# ideas.net
KiCad netlist of a schematic drawn in Altium Designer
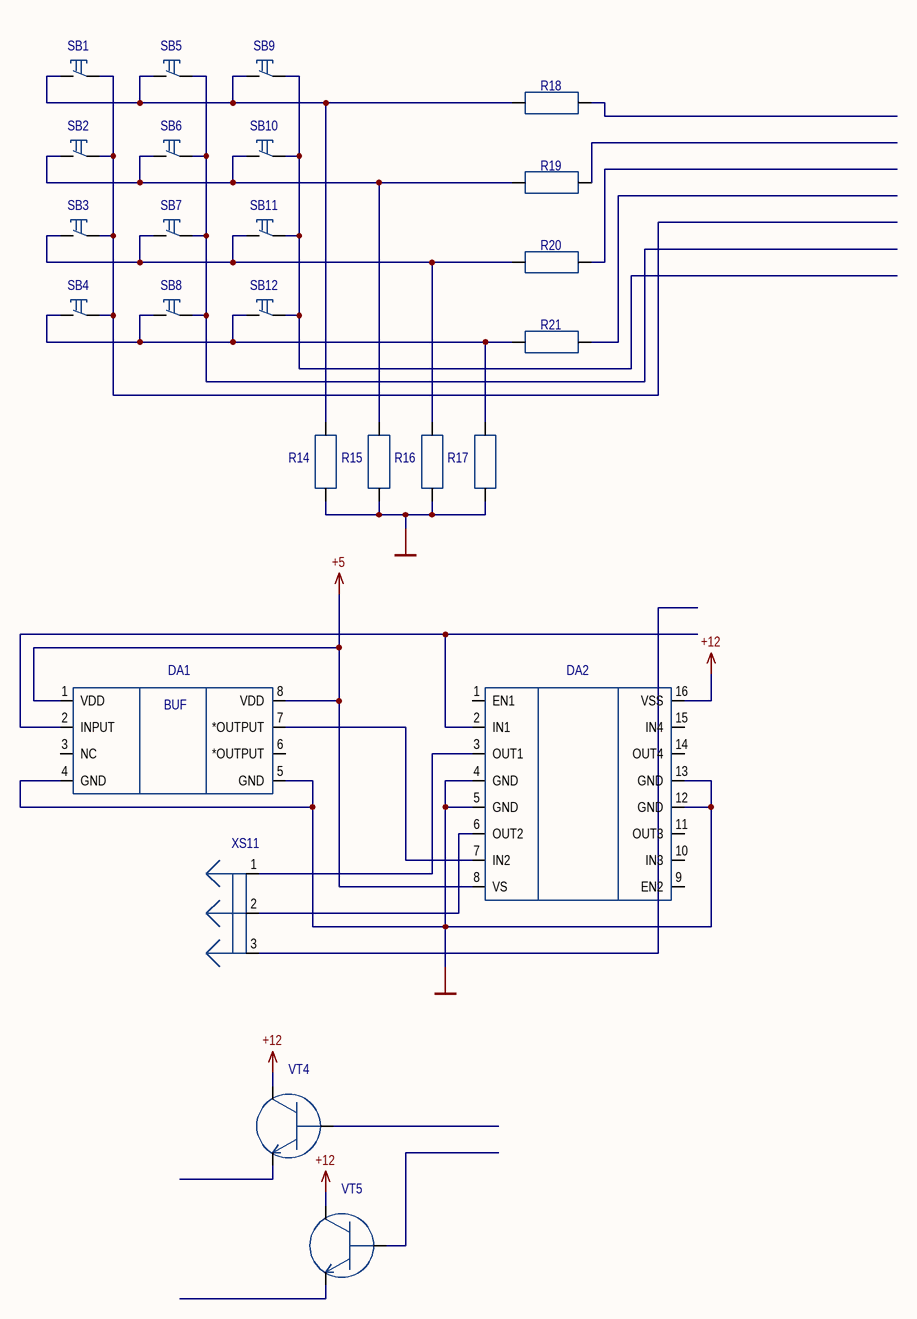
[diagram p0: ideas.SchDoc]

(export (version "E")
  (design (tool "Eeschema 10.0.6"))
  (components
    (comp (ref "DA1") (value "TC4421") (libsource (lib "diploma") (part "TC4421")))
    (comp (ref "DA2") (value "L293D") (libsource (lib "diploma") (part "L293D")))
    (comp (ref "R14") (value "res_100K") (libsource (lib "diploma") (part "res_100K")))
    (comp (ref "R15") (value "res_100K") (libsource (lib "diploma") (part "res_100K")))
    (comp (ref "R16") (value "res_100K") (libsource (lib "diploma") (part "res_100K")))
    (comp (ref "R17") (value "res_100K") (libsource (lib "diploma") (part "res_100K")))
    (comp (ref "R18") (value "res_1K") (libsource (lib "diploma") (part "res_1K")))
    (comp (ref "R19") (value "res_1K") (libsource (lib "diploma") (part "res_1K")))
    (comp (ref "R20") (value "res_1K") (libsource (lib "diploma") (part "res_1K")))
    (comp (ref "R21") (value "res_1K") (libsource (lib "diploma") (part "res_1K")))
    (comp (ref "SB1") (value "keypad_button") (libsource (lib "diploma") (part "keypad_button")))
    (comp (ref "SB2") (value "keypad_button") (libsource (lib "diploma") (part "keypad_button")))
    (comp (ref "SB3") (value "keypad_button") (libsource (lib "diploma") (part "keypad_button")))
    (comp (ref "SB4") (value "keypad_button") (libsource (lib "diploma") (part "keypad_button")))
    (comp (ref "SB5") (value "keypad_button") (libsource (lib "diploma") (part "keypad_button")))
    (comp (ref "SB6") (value "keypad_button") (libsource (lib "diploma") (part "keypad_button")))
    (comp (ref "SB7") (value "keypad_button") (libsource (lib "diploma") (part "keypad_button")))
    (comp (ref "SB8") (value "keypad_button") (libsource (lib "diploma") (part "keypad_button")))
    (comp (ref "SB9") (value "keypad_button") (libsource (lib "diploma") (part "keypad_button")))
    (comp (ref "SB10") (value "keypad_button") (libsource (lib "diploma") (part "keypad_button")))
    (comp (ref "SB11") (value "keypad_button") (libsource (lib "diploma") (part "keypad_button")))
    (comp (ref "SB12") (value "keypad_button") (libsource (lib "diploma") (part "keypad_button")))
    (comp (ref "VT4") (value "2N2926") (libsource (lib "diploma") (part "2N2926")))
    (comp (ref "VT5") (value "2N2926") (libsource (lib "diploma") (part "2N2926")))
    (comp (ref "XS11") (value "PWM_servo_connector") (libsource (lib "diploma") (part "PWM_servo_connector")))
  )
  (nets
    (net (code "1") (name "+5") (class "Default")
      (node (ref "DA1") (pin "1") (pinfunction "VDD_1") (pintype "passive"))
      (node (ref "DA1") (pin "8") (pinfunction "VDD_8") (pintype "passive"))
      (node (ref "DA2") (pin "8") (pinfunction "VS_8") (pintype "passive"))
    )
    (net (code "2") (name "+12") (class "Default")
      (node (ref "DA2") (pin "16") (pinfunction "VSS_16") (pintype "passive"))
      (node (ref "VT4") (pin "3") (pinfunction "C_3") (pintype "passive"))
      (node (ref "VT5") (pin "3") (pinfunction "C_3") (pintype "passive"))
    )
    (net (code "3") (name "GND") (class "Default")
      (node (ref "DA1") (pin "4") (pinfunction "GND_4") (pintype "passive"))
      (node (ref "DA1") (pin "5") (pinfunction "GND_5") (pintype "passive"))
      (node (ref "DA2") (pin "12") (pinfunction "GND_12") (pintype "passive"))
      (node (ref "DA2") (pin "13") (pinfunction "GND_13") (pintype "passive"))
      (node (ref "DA2") (pin "4") (pinfunction "GND_4") (pintype "passive"))
      (node (ref "DA2") (pin "5") (pinfunction "GND_5") (pintype "passive"))
      (node (ref "R14") (pin "1") (pinfunction "1_1") (pintype "passive"))
      (node (ref "R15") (pin "1") (pinfunction "1_1") (pintype "passive"))
      (node (ref "R16") (pin "1") (pinfunction "1_1") (pintype "passive"))
      (node (ref "R17") (pin "1") (pinfunction "1_1") (pintype "passive"))
    )
    (net (code "4") (name "Net-(DA1-INPUT)") (class "Default")
      (node (ref "DA1") (pin "2") (pinfunction "INPUT_2") (pintype "passive"))
      (node (ref "DA2") (pin "2") (pinfunction "IN1_2") (pintype "passive"))
    )
    (net (code "5") (name "Net-(DA2-IN2)") (class "Default")
      (node (ref "DA1") (pin "7") (pinfunction "*OUTPUT_7") (pintype "passive"))
      (node (ref "DA2") (pin "7") (pinfunction "IN2_7") (pintype "passive"))
    )
    (net (code "6") (name "Net-(DA2-OUT1)") (class "Default")
      (node (ref "DA2") (pin "3") (pinfunction "OUT1_3") (pintype "passive"))
      (node (ref "XS11") (pin "1") (pinfunction "1_1") (pintype "passive"))
    )
    (net (code "7") (name "Net-(DA2-OUT2)") (class "Default")
      (node (ref "DA2") (pin "6") (pinfunction "OUT2_6") (pintype "passive"))
      (node (ref "XS11") (pin "2") (pinfunction "2_2") (pintype "passive"))
    )
    (net (code "8") (name "Net-(R14-Pad2)") (class "Default")
      (node (ref "R14") (pin "2") (pinfunction "2_2") (pintype "passive"))
      (node (ref "R18") (pin "2") (pinfunction "2_2") (pintype "passive"))
      (node (ref "SB1") (pin "2") (pinfunction "2_2") (pintype "passive"))
      (node (ref "SB5") (pin "2") (pinfunction "2_2") (pintype "passive"))
      (node (ref "SB9") (pin "2") (pinfunction "2_2") (pintype "passive"))
    )
    (net (code "9") (name "Net-(R15-Pad2)") (class "Default")
      (node (ref "R15") (pin "2") (pinfunction "2_2") (pintype "passive"))
      (node (ref "R19") (pin "2") (pinfunction "2_2") (pintype "passive"))
      (node (ref "SB10") (pin "2") (pinfunction "2_2") (pintype "passive"))
      (node (ref "SB2") (pin "2") (pinfunction "2_2") (pintype "passive"))
      (node (ref "SB6") (pin "2") (pinfunction "2_2") (pintype "passive"))
    )
    (net (code "10") (name "Net-(R16-Pad2)") (class "Default")
      (node (ref "R16") (pin "2") (pinfunction "2_2") (pintype "passive"))
      (node (ref "R20") (pin "2") (pinfunction "2_2") (pintype "passive"))
      (node (ref "SB11") (pin "2") (pinfunction "2_2") (pintype "passive"))
      (node (ref "SB3") (pin "2") (pinfunction "2_2") (pintype "passive"))
      (node (ref "SB7") (pin "2") (pinfunction "2_2") (pintype "passive"))
    )
    (net (code "11") (name "Net-(R17-Pad2)") (class "Default")
      (node (ref "R17") (pin "2") (pinfunction "2_2") (pintype "passive"))
      (node (ref "R21") (pin "2") (pinfunction "2_2") (pintype "passive"))
      (node (ref "SB12") (pin "2") (pinfunction "2_2") (pintype "passive"))
      (node (ref "SB4") (pin "2") (pinfunction "2_2") (pintype "passive"))
      (node (ref "SB8") (pin "2") (pinfunction "2_2") (pintype "passive"))
    )
    (net (code "12") (name "Net-(SB1-Pad1)") (class "Default")
      (node (ref "SB1") (pin "1") (pinfunction "1_1") (pintype "passive"))
      (node (ref "SB2") (pin "1") (pinfunction "1_1") (pintype "passive"))
      (node (ref "SB3") (pin "1") (pinfunction "1_1") (pintype "passive"))
      (node (ref "SB4") (pin "1") (pinfunction "1_1") (pintype "passive"))
    )
    (net (code "13") (name "Net-(SB5-Pad1)") (class "Default")
      (node (ref "SB5") (pin "1") (pinfunction "1_1") (pintype "passive"))
      (node (ref "SB6") (pin "1") (pinfunction "1_1") (pintype "passive"))
      (node (ref "SB7") (pin "1") (pinfunction "1_1") (pintype "passive"))
      (node (ref "SB8") (pin "1") (pinfunction "1_1") (pintype "passive"))
    )
    (net (code "14") (name "Net-(SB10-Pad1)") (class "Default")
      (node (ref "SB10") (pin "1") (pinfunction "1_1") (pintype "passive"))
      (node (ref "SB11") (pin "1") (pinfunction "1_1") (pintype "passive"))
      (node (ref "SB12") (pin "1") (pinfunction "1_1") (pintype "passive"))
      (node (ref "SB9") (pin "1") (pinfunction "1_1") (pintype "passive"))
    )
    (net (code "15") (name "unconnected-(DA1-*OUTPUT-Pad6)") (class "Default")
      (node (ref "DA1") (pin "6") (pinfunction "*OUTPUT_6") (pintype "passive"))
    )
    (net (code "16") (name "unconnected-(DA1-NC-Pad3)") (class "Default")
      (node (ref "DA1") (pin "3") (pinfunction "NC_3") (pintype "passive"))
    )
    (net (code "17") (name "unconnected-(DA2-EN1-Pad1)") (class "Default")
      (node (ref "DA2") (pin "1") (pinfunction "EN1_1") (pintype "passive"))
    )
    (net (code "18") (name "unconnected-(DA2-EN2-Pad9)") (class "Default")
      (node (ref "DA2") (pin "9") (pinfunction "EN2_9") (pintype "passive"))
    )
    (net (code "19") (name "unconnected-(DA2-IN3-Pad10)") (class "Default")
      (node (ref "DA2") (pin "10") (pinfunction "IN3_10") (pintype "passive"))
    )
    (net (code "20") (name "unconnected-(DA2-IN4-Pad15)") (class "Default")
      (node (ref "DA2") (pin "15") (pinfunction "IN4_15") (pintype "passive"))
    )
    (net (code "21") (name "unconnected-(DA2-OUT3-Pad11)") (class "Default")
      (node (ref "DA2") (pin "11") (pinfunction "OUT3_11") (pintype "passive"))
    )
    (net (code "22") (name "unconnected-(DA2-OUT4-Pad14)") (class "Default")
      (node (ref "DA2") (pin "14") (pinfunction "OUT4_14") (pintype "passive"))
    )
    (net (code "23") (name "unconnected-(R18-Pad1)") (class "Default")
      (node (ref "R18") (pin "1") (pinfunction "1_1") (pintype "passive"))
    )
    (net (code "24") (name "unconnected-(R19-Pad1)") (class "Default")
      (node (ref "R19") (pin "1") (pinfunction "1_1") (pintype "passive"))
    )
    (net (code "25") (name "unconnected-(R20-Pad1)") (class "Default")
      (node (ref "R20") (pin "1") (pinfunction "1_1") (pintype "passive"))
    )
    (net (code "26") (name "unconnected-(R21-Pad1)") (class "Default")
      (node (ref "R21") (pin "1") (pinfunction "1_1") (pintype "passive"))
    )
    (net (code "27") (name "unconnected-(VT4-B-Pad2)") (class "Default")
      (node (ref "VT4") (pin "2") (pinfunction "B_2") (pintype "passive"))
    )
    (net (code "28") (name "unconnected-(VT4-E-Pad1)") (class "Default")
      (node (ref "VT4") (pin "1") (pinfunction "E_1") (pintype "passive"))
    )
    (net (code "29") (name "unconnected-(VT5-B-Pad2)") (class "Default")
      (node (ref "VT5") (pin "2") (pinfunction "B_2") (pintype "passive"))
    )
    (net (code "30") (name "unconnected-(VT5-E-Pad1)") (class "Default")
      (node (ref "VT5") (pin "1") (pinfunction "E_1") (pintype "passive"))
    )
    (net (code "31") (name "unconnected-(XS11-Pad3)") (class "Default")
      (node (ref "XS11") (pin "3") (pinfunction "3_3") (pintype "passive"))
    )
  )
)
